# main.net
KiCad netlist of a schematic drawn in EAGLE
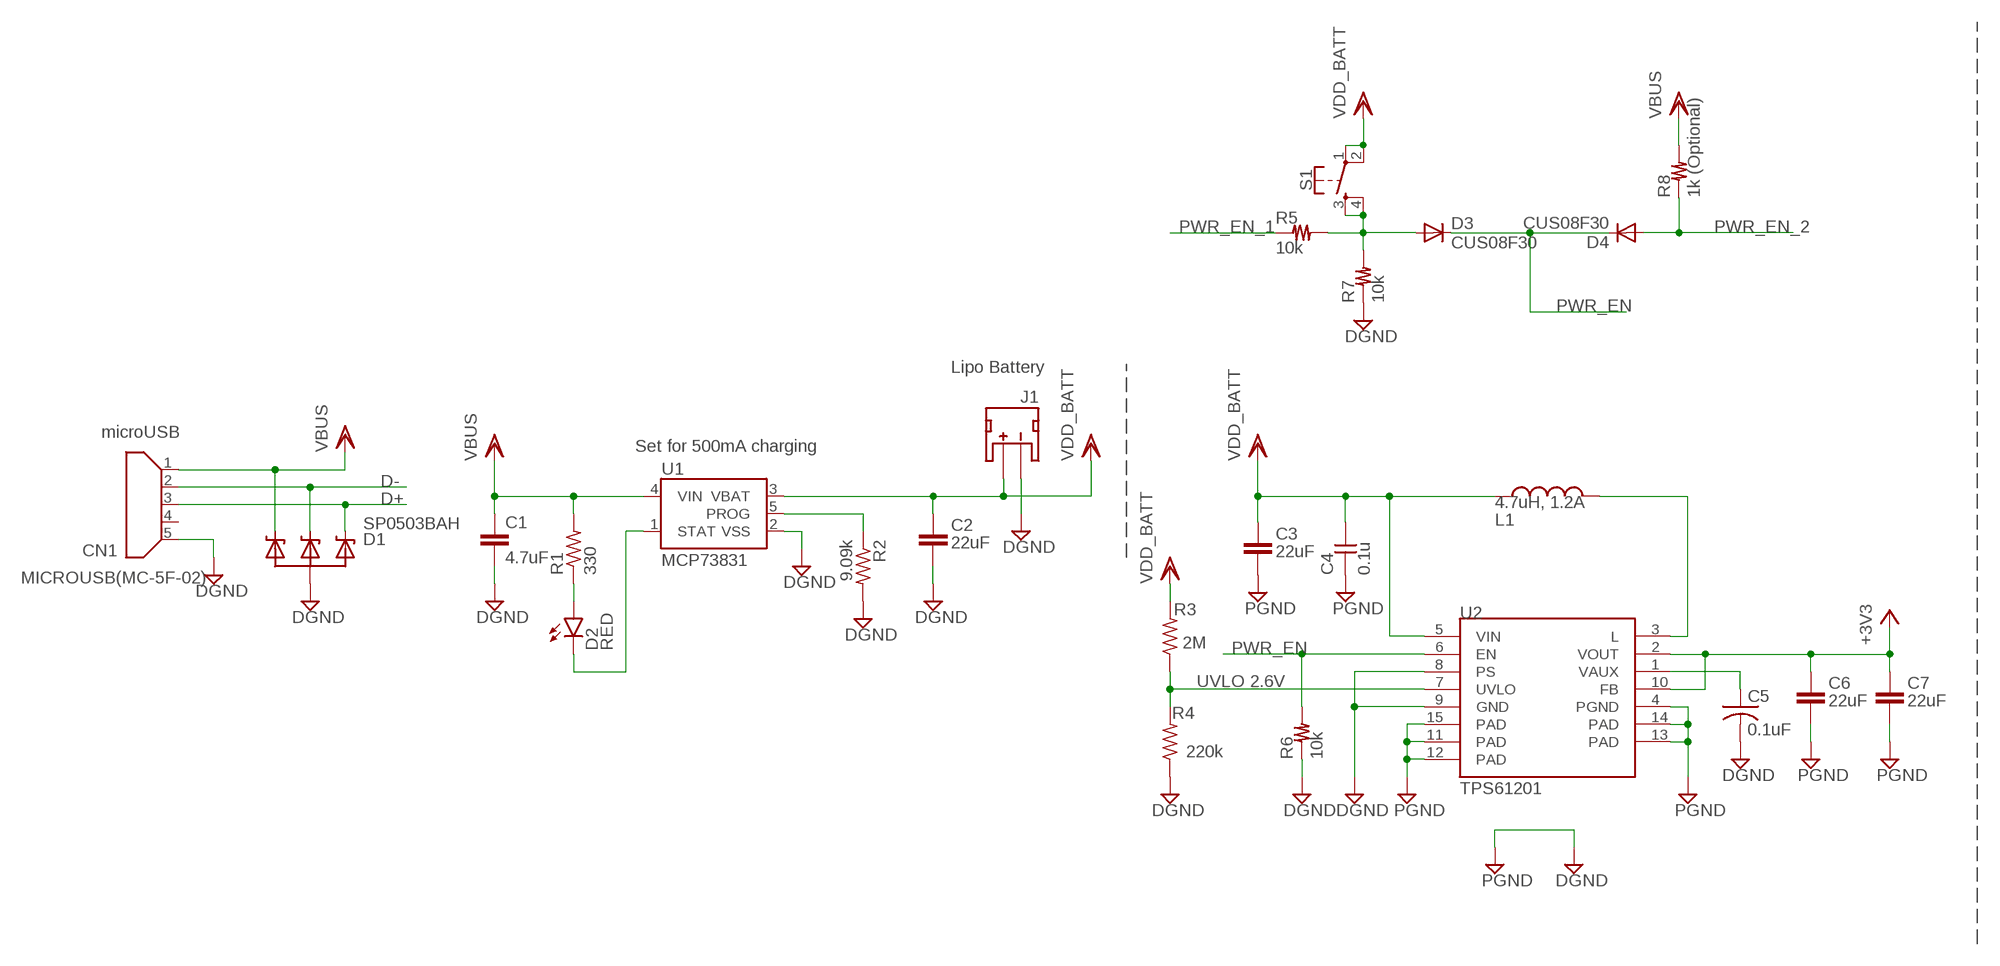
[diagram p0: schematic, sheet 1, part 1 of 2]
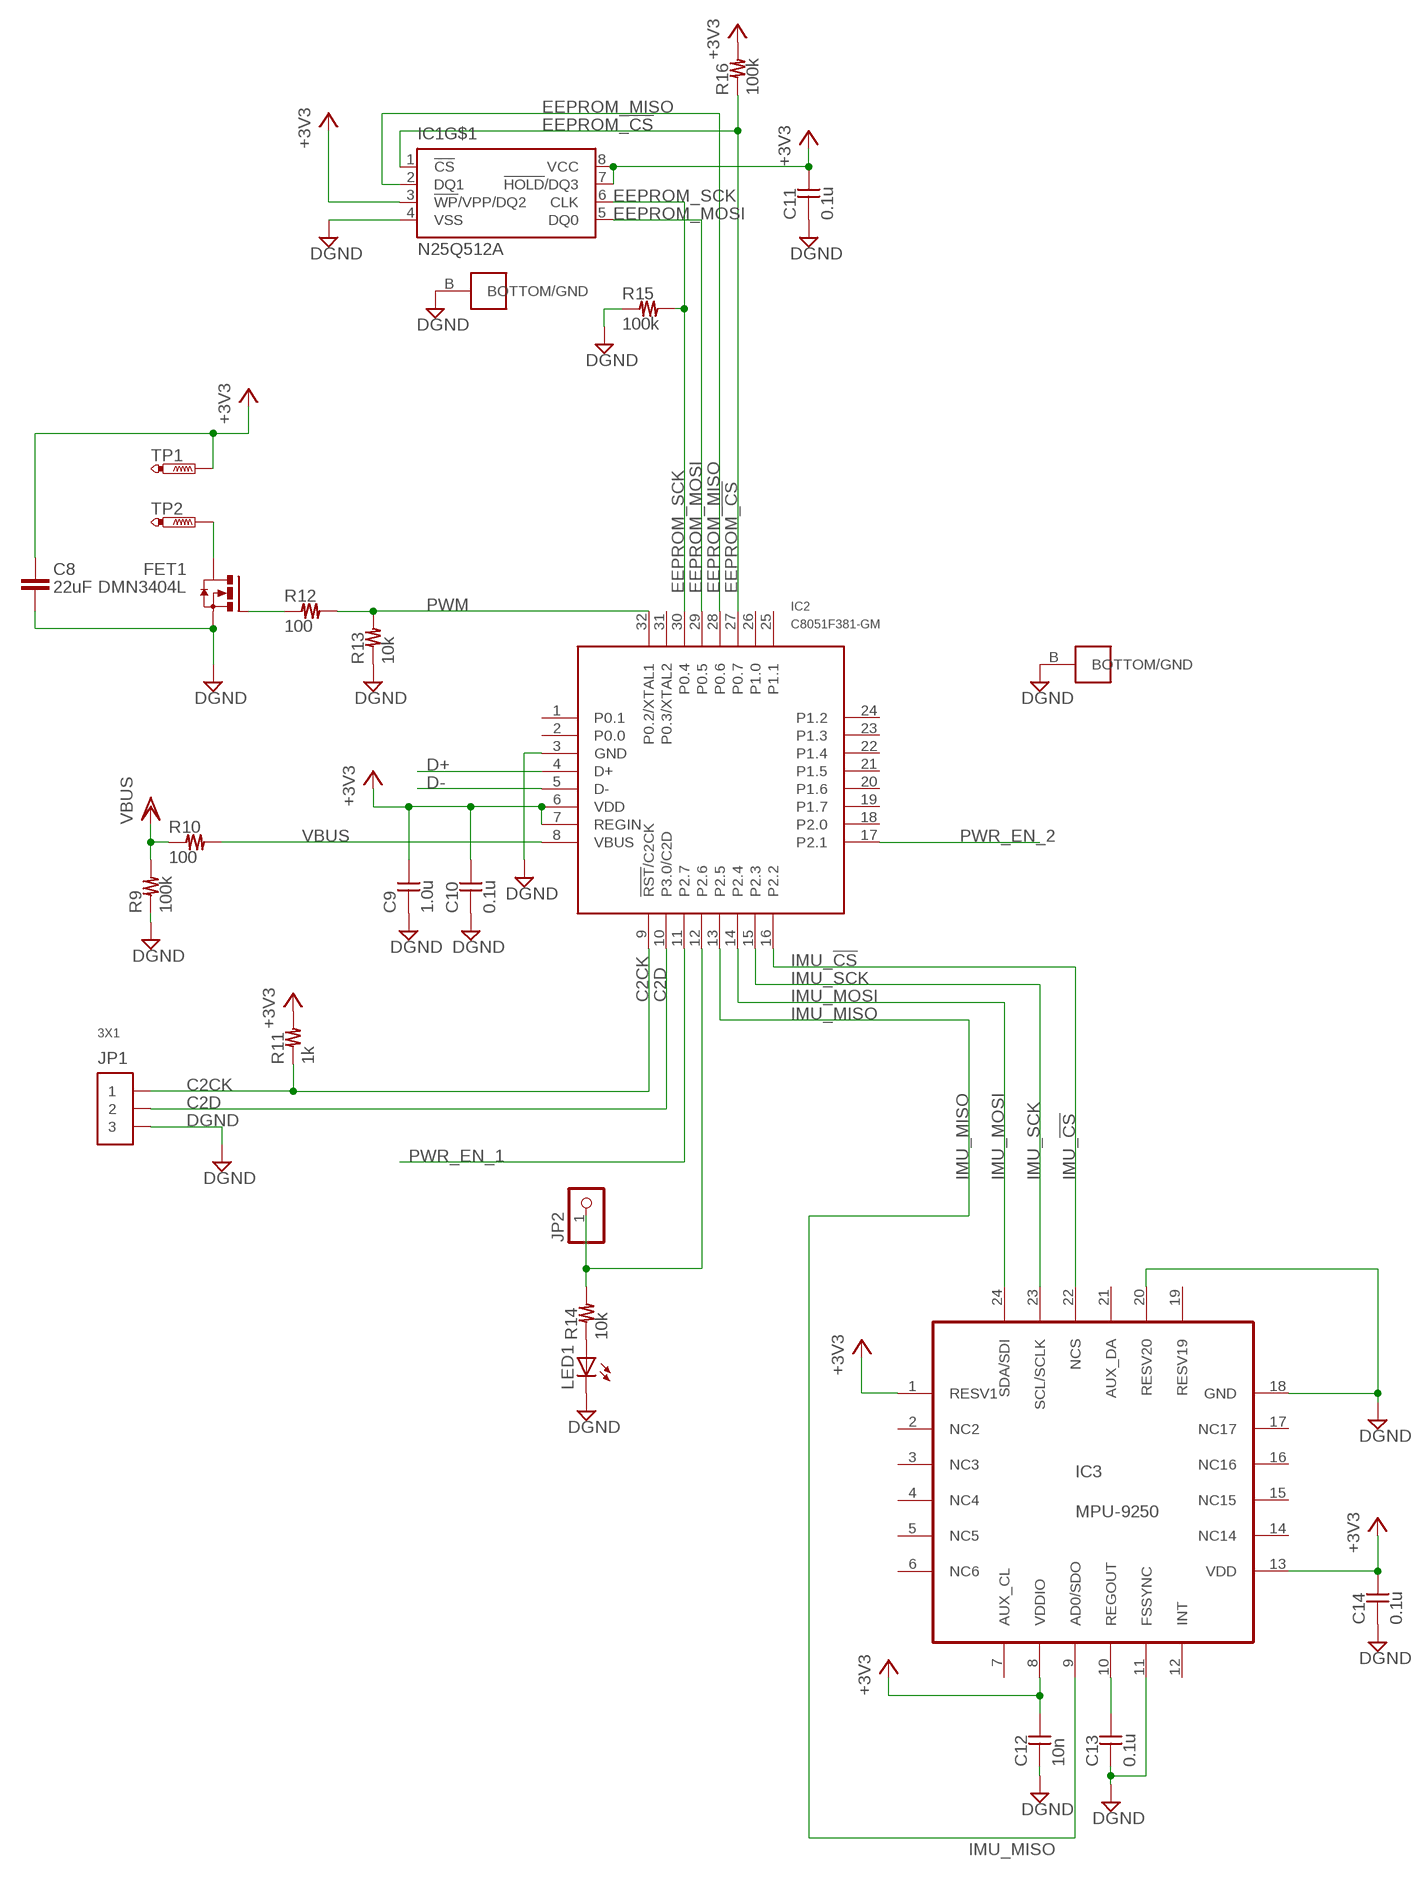
[diagram p1: schematic, sheet 1, part 2 of 2]

(export (version "E")
  (design (tool "Eeschema 10.0.6"))
  (components
    (comp (ref "C1")
      (value "4.7uF")
      (footprint "eagle-import:0603-CAP")
      (libsource (lib "eagle-import") (part "4.7UF-6.3V-10%(0603)0603"))
    )
    (comp (ref "C2")
      (value "22uF")
      (footprint "eagle-import:0805")
      (libsource (lib "eagle-import") (part "CAP0805"))
    )
    (comp (ref "C3")
      (value "22uF")
      (footprint "eagle-import:0805")
      (libsource (lib "eagle-import") (part "CAP0805"))
    )
    (comp (ref "C4")
      (value "0.1u")
      (footprint "eagle-import:1005")
      (libsource (lib "eagle-import") (part "C-1005"))
    )
    (comp (ref "C5")
      (value "0.1uF")
      (footprint "eagle-import:C0402K")
      (libsource (lib "eagle-import") (part "C-USC0402K"))
    )
    (comp (ref "C6")
      (value "22uF")
      (footprint "eagle-import:0805")
      (libsource (lib "eagle-import") (part "CAP0805"))
    )
    (comp (ref "C7")
      (value "22uF")
      (footprint "eagle-import:0805")
      (libsource (lib "eagle-import") (part "CAP0805"))
    )
    (comp (ref "C8")
      (value "22uF")
      (footprint "eagle-import:0805")
      (libsource (lib "eagle-import") (part "CAP0805"))
    )
    (comp (ref "C9")
      (value "1.0u")
      (footprint "eagle-import:1005")
      (libsource (lib "eagle-import") (part "C-1005"))
    )
    (comp (ref "C10")
      (value "0.1u")
      (footprint "eagle-import:1005")
      (libsource (lib "eagle-import") (part "C-1005"))
    )
    (comp (ref "C11")
      (value "0.1u")
      (footprint "eagle-import:1005")
      (libsource (lib "eagle-import") (part "C-1005"))
    )
    (comp (ref "C12")
      (value "10n")
      (footprint "eagle-import:1005")
      (libsource (lib "eagle-import") (part "C-1005"))
    )
    (comp (ref "C13")
      (value "0.1u")
      (footprint "eagle-import:1005")
      (libsource (lib "eagle-import") (part "C-1005"))
    )
    (comp (ref "C14")
      (value "0.1u")
      (footprint "eagle-import:1005")
      (libsource (lib "eagle-import") (part "C-1005"))
    )
    (comp (ref "CN1")
      (value "MICROUSB(MC-5F-02)")
      (footprint "eagle-import:MICROUSB(MC-5F-02)")
      (libsource (lib "eagle-import") (part "MICROUSB(MC-5F-02)"))
    )
    (comp (ref "D1")
      (value "SP0503BAH")
      (footprint "eagle-import:SOT143")
      (libsource (lib "eagle-import") (part "SP0503BAH"))
    )
    (comp (ref "D2")
      (value "RED")
      (footprint "eagle-import:LED-0603")
      (libsource (lib "eagle-import") (part "LED-RED0603"))
    )
    (comp (ref "D3")
      (value "CUS08F30")
      (footprint "eagle-import:SOD323-W")
      (libsource (lib "eagle-import") (part "DIODE-SOD323-W"))
    )
    (comp (ref "D4")
      (value "CUS08F30")
      (footprint "eagle-import:SOD323-W")
      (libsource (lib "eagle-import") (part "DIODE-SOD323-W"))
    )
    (comp (ref "FET1")
      (value "DMN3404L")
      (footprint "eagle-import:SOT23")
      (libsource (lib "eagle-import") (part "DMN3404L"))
    )
    (comp (ref "IC1")
      (value "N25Q512A")
      (footprint "eagle-import:V-PDFN-8")
      (libsource (lib "eagle-import") (part "N25Q512A"))
    )
    (comp (ref "IC2")
      (value "C8051F381-GM")
      (footprint "eagle-import:QFN32")
      (libsource (lib "eagle-import") (part "C8051F381-GM"))
    )
    (comp (ref "IC3")
      (value "MPU-9250")
      (footprint "eagle-import:QFN-24")
      (libsource (lib "eagle-import") (part "MPU-9250"))
    )
    (comp (ref "J1")
      (value "JST")
      (footprint "eagle-import:JST-2-SMD")
      (libsource (lib "eagle-import") (part "JST_2MM_MALE"))
    )
    (comp (ref "JP1")
      (value "3X1")
      (footprint "eagle-import:MA3-1")
      (libsource (lib "eagle-import") (part "3X1"))
    )
    (comp (ref "JP2")
      (value "PINHD-1X1")
      (footprint "eagle-import:1X01")
      (libsource (lib "eagle-import") (part "PINHD-1X1"))
    )
    (comp (ref "L1")
      (value "4.7uH, 1.2A")
      (footprint "eagle-import:CDRH2D09")
      (libsource (lib "eagle-import") (part "INDUCTOR."))
    )
    (comp (ref "LED1")
      (value "LED1608O")
      (footprint "eagle-import:1608-OLI")
      (libsource (lib "eagle-import") (part "LED1608O"))
    )
    (comp (ref "R1")
      (value "330")
      (footprint "eagle-import:R0402")
      (libsource (lib "eagle-import") (part "R-US_R0402"))
    )
    (comp (ref "R2")
      (value "9.09k")
      (footprint "eagle-import:R0402")
      (libsource (lib "eagle-import") (part "R-US_R0402"))
    )
    (comp (ref "R3")
      (value "2M")
      (footprint "eagle-import:R0402")
      (libsource (lib "eagle-import") (part "R-US_R0402"))
    )
    (comp (ref "R4")
      (value "220k")
      (footprint "eagle-import:R0402")
      (libsource (lib "eagle-import") (part "R-US_R0402"))
    )
    (comp (ref "R5")
      (value "10k")
      (footprint "eagle-import:1005")
      (libsource (lib "eagle-import") (part "R-1005"))
    )
    (comp (ref "R6")
      (value "10k")
      (footprint "eagle-import:1005")
      (libsource (lib "eagle-import") (part "R-1005"))
    )
    (comp (ref "R7")
      (value "10k")
      (footprint "eagle-import:1005")
      (libsource (lib "eagle-import") (part "R-1005"))
    )
    (comp (ref "R8")
      (value "1k (Optional)")
      (footprint "eagle-import:1005")
      (libsource (lib "eagle-import") (part "R-1005"))
    )
    (comp (ref "R9")
      (value "100k")
      (footprint "eagle-import:1005")
      (libsource (lib "eagle-import") (part "R-1005"))
    )
    (comp (ref "R10")
      (value "100")
      (footprint "eagle-import:1005")
      (libsource (lib "eagle-import") (part "R-1005"))
    )
    (comp (ref "R11")
      (value "1k")
      (footprint "eagle-import:1005")
      (libsource (lib "eagle-import") (part "R-1005"))
    )
    (comp (ref "R12")
      (value "100")
      (footprint "eagle-import:1005")
      (libsource (lib "eagle-import") (part "R-1005"))
    )
    (comp (ref "R13")
      (value "10k")
      (footprint "eagle-import:1005")
      (libsource (lib "eagle-import") (part "R-1005"))
    )
    (comp (ref "R14")
      (value "10k")
      (footprint "eagle-import:1005")
      (libsource (lib "eagle-import") (part "R-1005"))
    )
    (comp (ref "R15")
      (value "100k")
      (footprint "eagle-import:1005")
      (libsource (lib "eagle-import") (part "R-1005"))
    )
    (comp (ref "R16")
      (value "100k")
      (footprint "eagle-import:1005")
      (libsource (lib "eagle-import") (part "R-1005"))
    )
    (comp (ref "S1")
      (value "MOMENTARY-SWITCH-SPST-2-SMD-4.6X2.8MM")
      (footprint "eagle-import:TACTILE_SWITCH_SMD_4.6X2.8MM")
      (libsource (lib "eagle-import") (part "MOMENTARY-SWITCH-SPST-2-SMD-4.6X2.8MM"))
    )
    (comp (ref "TP1")
      (value "PTR1TP10R")
      (footprint "eagle-import:TP10R")
      (libsource (lib "eagle-import") (part "PTR1TP10R"))
    )
    (comp (ref "TP2")
      (value "PTR1TP10R")
      (footprint "eagle-import:TP10R")
      (libsource (lib "eagle-import") (part "PTR1TP10R"))
    )
    (comp (ref "U1")
      (value "MCP73831")
      (footprint "eagle-import:SOT23-5")
      (libsource (lib "eagle-import") (part "MCP73831"))
    )
    (comp (ref "U2")
      (value "TPS61201")
      (footprint "eagle-import:QFN-10_PAD")
      (libsource (lib "eagle-import") (part "TPS61200"))
    )
  )
  (nets
    (net (code "1") (name "+3V3") (class "Default")
      (node (ref "C10") (pin "P$2") (pinfunction "P$2_P$2") (pintype "passive"))
      (node (ref "C11") (pin "P$2") (pinfunction "P$2_P$2") (pintype "passive"))
      (node (ref "C12") (pin "P$2") (pinfunction "P$2_P$2") (pintype "passive"))
      (node (ref "C14") (pin "P$2") (pinfunction "P$2_P$2") (pintype "passive"))
      (node (ref "C6") (pin "1") (pinfunction "1_1") (pintype "passive"))
      (node (ref "C7") (pin "1") (pinfunction "1_1") (pintype "passive"))
      (node (ref "C8") (pin "1") (pinfunction "1_1") (pintype "passive"))
      (node (ref "C9") (pin "P$2") (pinfunction "P$2_P$2") (pintype "passive"))
      (node (ref "IC1") (pin "3") (pinfunction "~{WP}/VPP/DQ2_3") (pintype "bidirectional"))
      (node (ref "IC1") (pin "7") (pinfunction "~{HOLD}/DQ3_7") (pintype "bidirectional"))
      (node (ref "IC1") (pin "8") (pinfunction "VCC_8") (pintype "power_in"))
      (node (ref "IC2") (pin "6") (pinfunction "VDD_6") (pintype "bidirectional"))
      (node (ref "IC2") (pin "7") (pinfunction "REGIN_7") (pintype "bidirectional"))
      (node (ref "IC3") (pin "1") (pinfunction "RESV1_1") (pintype "input"))
      (node (ref "IC3") (pin "13") (pinfunction "VDD_13") (pintype "power_in"))
      (node (ref "IC3") (pin "8") (pinfunction "VDDIO_8") (pintype "power_in"))
      (node (ref "R11") (pin "P$2") (pinfunction "P$2_P$2") (pintype "passive"))
      (node (ref "R16") (pin "P$2") (pinfunction "P$2_P$2") (pintype "passive"))
      (node (ref "TP1") (pin "TP") (pinfunction "TP_TP") (pintype "input"))
      (node (ref "U2") (pin "10") (pinfunction "FB_10") (pintype "passive"))
      (node (ref "U2") (pin "2") (pinfunction "VOUT_2") (pintype "passive"))
    )
    (net (code "2") (name "/C2CK") (class "Default")
      (node (ref "IC2") (pin "9") (pinfunction "~{RST}/C2CK_9") (pintype "bidirectional"))
      (node (ref "JP1") (pin "1") (pinfunction "1_1") (pintype "passive"))
      (node (ref "R11") (pin "P$1") (pinfunction "P$1_P$1") (pintype "passive"))
    )
    (net (code "3") (name "/C2D") (class "Default")
      (node (ref "IC2") (pin "10") (pinfunction "P3.0/C2D_10") (pintype "bidirectional"))
      (node (ref "JP1") (pin "2") (pinfunction "2_2") (pintype "passive"))
    )
    (net (code "4") (name "/D+") (class "Default")
      (node (ref "CN1") (pin "3") (pinfunction "P$3_3") (pintype "passive"))
      (node (ref "D1") (pin "2") (pinfunction "2_2") (pintype "passive"))
      (node (ref "IC2") (pin "4") (pinfunction "D+_4") (pintype "bidirectional"))
    )
    (net (code "5") (name "/D-") (class "Default")
      (node (ref "CN1") (pin "2") (pinfunction "P$2_2") (pintype "passive"))
      (node (ref "D1") (pin "3") (pinfunction "3_3") (pintype "passive"))
      (node (ref "IC2") (pin "5") (pinfunction "D-_5") (pintype "bidirectional"))
    )
    (net (code "6") (name "/EEPROM_MISO") (class "Default")
      (node (ref "IC1") (pin "2") (pinfunction "DQ1_2") (pintype "bidirectional"))
      (node (ref "IC2") (pin "28") (pinfunction "P0.6_28") (pintype "bidirectional"))
    )
    (net (code "7") (name "/EEPROM_MOSI") (class "Default")
      (node (ref "IC1") (pin "5") (pinfunction "DQ0_5") (pintype "bidirectional"))
      (node (ref "IC2") (pin "29") (pinfunction "P0.5_29") (pintype "bidirectional"))
    )
    (net (code "8") (name "/EEPROM_SCK") (class "Default")
      (node (ref "IC1") (pin "6") (pinfunction "CLK_6") (pintype "input"))
      (node (ref "IC2") (pin "30") (pinfunction "P0.4_30") (pintype "bidirectional"))
      (node (ref "R15") (pin "P$2") (pinfunction "P$2_P$2") (pintype "passive"))
    )
    (net (code "9") (name "/EEPROM_~{CS}") (class "Default")
      (node (ref "IC1") (pin "1") (pinfunction "~{CS}_1") (pintype "input"))
      (node (ref "IC2") (pin "27") (pinfunction "P0.7_27") (pintype "bidirectional"))
      (node (ref "R16") (pin "P$1") (pinfunction "P$1_P$1") (pintype "passive"))
    )
    (net (code "10") (name "/IMU_MISO") (class "Default")
      (node (ref "IC2") (pin "13") (pinfunction "P2.5_13") (pintype "bidirectional"))
      (node (ref "IC3") (pin "9") (pinfunction "AD0/SDO_9") (pintype "bidirectional"))
    )
    (net (code "11") (name "/IMU_MOSI") (class "Default")
      (node (ref "IC2") (pin "14") (pinfunction "P2.4_14") (pintype "bidirectional"))
      (node (ref "IC3") (pin "24") (pinfunction "SDA/SDI_24") (pintype "input"))
    )
    (net (code "12") (name "/IMU_SCK") (class "Default")
      (node (ref "IC2") (pin "15") (pinfunction "P2.3_15") (pintype "bidirectional"))
      (node (ref "IC3") (pin "23") (pinfunction "SCL/SCLK_23") (pintype "input"))
    )
    (net (code "13") (name "/IMU_~{CS}") (class "Default")
      (node (ref "IC2") (pin "16") (pinfunction "P2.2_16") (pintype "bidirectional"))
      (node (ref "IC3") (pin "22") (pinfunction "NCS_22") (pintype "input"))
    )
    (net (code "14") (name "/PWM") (class "Default")
      (node (ref "IC2") (pin "32") (pinfunction "P0.2/XTAL1_32") (pintype "bidirectional"))
      (node (ref "R12") (pin "P$2") (pinfunction "P$2_P$2") (pintype "passive"))
      (node (ref "R13") (pin "P$2") (pinfunction "P$2_P$2") (pintype "passive"))
    )
    (net (code "15") (name "/PWR_EN") (class "Default")
      (node (ref "D3") (pin "C") (pinfunction "C_C") (pintype "passive"))
      (node (ref "D4") (pin "C") (pinfunction "C_C") (pintype "passive"))
      (node (ref "R6") (pin "P$2") (pinfunction "P$2_P$2") (pintype "passive"))
      (node (ref "U2") (pin "6") (pinfunction "EN_6") (pintype "input"))
    )
    (net (code "16") (name "/PWR_EN_1") (class "Default")
      (node (ref "IC2") (pin "11") (pinfunction "P2.7_11") (pintype "bidirectional"))
      (node (ref "R5") (pin "P$1") (pinfunction "P$1_P$1") (pintype "passive"))
    )
    (net (code "17") (name "/PWR_EN_2") (class "Default")
      (node (ref "D4") (pin "A") (pinfunction "A_A") (pintype "passive"))
      (node (ref "IC2") (pin "17") (pinfunction "P2.1_17") (pintype "bidirectional"))
      (node (ref "R8") (pin "P$1") (pinfunction "P$1_P$1") (pintype "passive"))
    )
    (net (code "18") (name "DGND") (class "Default")
      (node (ref "C1") (pin "2") (pinfunction "2_2") (pintype "passive"))
      (node (ref "C10") (pin "P$1") (pinfunction "P$1_P$1") (pintype "passive"))
      (node (ref "C11") (pin "P$1") (pinfunction "P$1_P$1") (pintype "passive"))
      (node (ref "C12") (pin "P$1") (pinfunction "P$1_P$1") (pintype "passive"))
      (node (ref "C13") (pin "P$1") (pinfunction "P$1_P$1") (pintype "passive"))
      (node (ref "C14") (pin "P$1") (pinfunction "P$1_P$1") (pintype "passive"))
      (node (ref "C2") (pin "2") (pinfunction "2_2") (pintype "passive"))
      (node (ref "C3") (pin "2") (pinfunction "2_2") (pintype "passive"))
      (node (ref "C4") (pin "P$1") (pinfunction "P$1_P$1") (pintype "passive"))
      (node (ref "C5") (pin "2") (pinfunction "2_2") (pintype "passive"))
      (node (ref "C6") (pin "2") (pinfunction "2_2") (pintype "passive"))
      (node (ref "C7") (pin "2") (pinfunction "2_2") (pintype "passive"))
      (node (ref "C8") (pin "2") (pinfunction "2_2") (pintype "passive"))
      (node (ref "C9") (pin "P$1") (pinfunction "P$1_P$1") (pintype "passive"))
      (node (ref "CN1") (pin "5") (pinfunction "P$5_5") (pintype "passive"))
      (node (ref "D1") (pin "1") (pinfunction "1_1") (pintype "passive"))
      (node (ref "FET1") (pin "S") (pinfunction "S_S") (pintype "passive"))
      (node (ref "IC1") (pin "4") (pinfunction "VSS_4") (pintype "power_in"))
      (node (ref "IC1") (pin "B") (pinfunction "BOTTOM/GND_B") (pintype "power_in"))
      (node (ref "IC2") (pin "3") (pinfunction "GND_3") (pintype "bidirectional"))
      (node (ref "IC2") (pin "B") (pinfunction "BOTTOM/GND_B") (pintype "power_in"))
      (node (ref "IC3") (pin "11") (pinfunction "FSSYNC_11") (pintype "input"))
      (node (ref "IC3") (pin "18") (pinfunction "GND_18") (pintype "power_in"))
      (node (ref "IC3") (pin "20") (pinfunction "RESV20_20") (pintype "input"))
      (node (ref "J1") (pin "1") (pinfunction "-_1") (pintype "bidirectional"))
      (node (ref "JP1") (pin "3") (pinfunction "3_3") (pintype "passive"))
      (node (ref "LED1") (pin "K") (pinfunction "K_K") (pintype "passive"))
      (node (ref "R13") (pin "P$1") (pinfunction "P$1_P$1") (pintype "passive"))
      (node (ref "R15") (pin "P$1") (pinfunction "P$1_P$1") (pintype "passive"))
      (node (ref "R2") (pin "2") (pinfunction "2_2") (pintype "passive"))
      (node (ref "R4") (pin "1") (pinfunction "1_1") (pintype "passive"))
      (node (ref "R6") (pin "P$1") (pinfunction "P$1_P$1") (pintype "passive"))
      (node (ref "R7") (pin "P$1") (pinfunction "P$1_P$1") (pintype "passive"))
      (node (ref "R9") (pin "P$1") (pinfunction "P$1_P$1") (pintype "passive"))
      (node (ref "U1") (pin "2") (pinfunction "VSS_2") (pintype "power_in"))
      (node (ref "U2") (pin "11") (pinfunction "PAD_11") (pintype "power_in"))
      (node (ref "U2") (pin "12") (pinfunction "PAD_12") (pintype "power_in"))
      (node (ref "U2") (pin "13") (pinfunction "PAD_13") (pintype "power_in"))
      (node (ref "U2") (pin "14") (pinfunction "PAD_14") (pintype "power_in"))
      (node (ref "U2") (pin "15") (pinfunction "PAD_15") (pintype "power_in"))
      (node (ref "U2") (pin "4") (pinfunction "PGND_4") (pintype "power_in"))
      (node (ref "U2") (pin "8") (pinfunction "PS_8") (pintype "input"))
      (node (ref "U2") (pin "9") (pinfunction "GND_9") (pintype "power_in"))
    )
    (net (code "19") (name "Net-(D2-PadA)") (class "Default")
      (node (ref "D2") (pin "A") (pinfunction "A_A") (pintype "passive"))
      (node (ref "R1") (pin "1") (pinfunction "1_1") (pintype "passive"))
    )
    (net (code "20") (name "Net-(D3-PadA)") (class "Default")
      (node (ref "D3") (pin "A") (pinfunction "A_A") (pintype "passive"))
      (node (ref "R5") (pin "P$2") (pinfunction "P$2_P$2") (pintype "passive"))
      (node (ref "R7") (pin "P$2") (pinfunction "P$2_P$2") (pintype "passive"))
      (node (ref "S1") (pin "3") (pinfunction "3_3") (pintype "passive"))
      (node (ref "S1") (pin "4") (pinfunction "4_4") (pintype "passive"))
    )
    (net (code "21") (name "Net-(FET1-PadD)") (class "Default")
      (node (ref "FET1") (pin "D") (pinfunction "D_D") (pintype "passive"))
      (node (ref "TP2") (pin "TP") (pinfunction "TP_TP") (pintype "input"))
    )
    (net (code "22") (name "Net-(FET1-PadG)") (class "Default")
      (node (ref "FET1") (pin "G") (pinfunction "G_G") (pintype "passive"))
      (node (ref "R12") (pin "P$1") (pinfunction "P$1_P$1") (pintype "passive"))
    )
    (net (code "23") (name "Net-(IC2A-P2.6)") (class "Default")
      (node (ref "IC2") (pin "12") (pinfunction "P2.6_12") (pintype "bidirectional"))
      (node (ref "JP2") (pin "1") (pinfunction "1_1") (pintype "passive"))
      (node (ref "R14") (pin "P$2") (pinfunction "P$2_P$2") (pintype "passive"))
    )
    (net (code "24") (name "Net-(IC2A-VBUS)") (class "Default")
      (node (ref "IC2") (pin "8") (pinfunction "VBUS_8") (pintype "bidirectional"))
      (node (ref "R10") (pin "P$2") (pinfunction "P$2_P$2") (pintype "passive"))
    )
    (net (code "25") (name "Net-(IC3-REGOUT)") (class "Default")
      (node (ref "C13") (pin "P$2") (pinfunction "P$2_P$2") (pintype "passive"))
      (node (ref "IC3") (pin "10") (pinfunction "REGOUT_10") (pintype "bidirectional"))
    )
    (net (code "26") (name "Net-(L1-1)") (class "Default")
      (node (ref "L1") (pin "P$1") (pinfunction "1_P$1") (pintype "passive"))
      (node (ref "U2") (pin "3") (pinfunction "L_3") (pintype "passive"))
    )
    (net (code "27") (name "Net-(LED1-PadA)") (class "Default")
      (node (ref "LED1") (pin "A") (pinfunction "A_A") (pintype "passive"))
      (node (ref "R14") (pin "P$1") (pinfunction "P$1_P$1") (pintype "passive"))
    )
    (net (code "28") (name "Net-(U1-PROG)") (class "Default")
      (node (ref "R2") (pin "1") (pinfunction "1_1") (pintype "passive"))
      (node (ref "U1") (pin "5") (pinfunction "PROG_5") (pintype "input"))
    )
    (net (code "29") (name "Net-(U1-STAT)") (class "Default")
      (node (ref "D2") (pin "C") (pinfunction "C_C") (pintype "passive"))
      (node (ref "U1") (pin "1") (pinfunction "STAT_1") (pintype "output"))
    )
    (net (code "30") (name "Net-(U2-UVLO)") (class "Default")
      (node (ref "R3") (pin "1") (pinfunction "1_1") (pintype "passive"))
      (node (ref "R4") (pin "2") (pinfunction "2_2") (pintype "passive"))
      (node (ref "U2") (pin "7") (pinfunction "UVLO_7") (pintype "passive"))
    )
    (net (code "31") (name "Net-(U2-VAUX)") (class "Default")
      (node (ref "C5") (pin "1") (pinfunction "1_1") (pintype "passive"))
      (node (ref "U2") (pin "1") (pinfunction "VAUX_1") (pintype "passive"))
    )
    (net (code "32") (name "VBUS") (class "Default")
      (node (ref "C1") (pin "1") (pinfunction "1_1") (pintype "passive"))
      (node (ref "CN1") (pin "1") (pinfunction "P$1_1") (pintype "passive"))
      (node (ref "D1") (pin "4") (pinfunction "4_4") (pintype "passive"))
      (node (ref "R1") (pin "2") (pinfunction "2_2") (pintype "passive"))
      (node (ref "R10") (pin "P$1") (pinfunction "P$1_P$1") (pintype "passive"))
      (node (ref "R8") (pin "P$2") (pinfunction "P$2_P$2") (pintype "passive"))
      (node (ref "R9") (pin "P$2") (pinfunction "P$2_P$2") (pintype "passive"))
      (node (ref "U1") (pin "4") (pinfunction "VIN_4") (pintype "power_in"))
    )
    (net (code "33") (name "VDD_BATT") (class "Default")
      (node (ref "C2") (pin "1") (pinfunction "1_1") (pintype "passive"))
      (node (ref "C3") (pin "1") (pinfunction "1_1") (pintype "passive"))
      (node (ref "C4") (pin "P$2") (pinfunction "P$2_P$2") (pintype "passive"))
      (node (ref "J1") (pin "2") (pinfunction "+_2") (pintype "bidirectional"))
      (node (ref "L1") (pin "P$2") (pinfunction "2_P$2") (pintype "passive"))
      (node (ref "R3") (pin "2") (pinfunction "2_2") (pintype "passive"))
      (node (ref "S1") (pin "1") (pinfunction "1_1") (pintype "passive"))
      (node (ref "S1") (pin "2") (pinfunction "2_2") (pintype "passive"))
      (node (ref "U1") (pin "3") (pinfunction "VBAT_3") (pintype "power_in"))
      (node (ref "U2") (pin "5") (pinfunction "VIN_5") (pintype "power_in"))
    )
    (net (code "34") (name "unconnected-(CN1-P$4-Pad4)") (class "Default")
      (node (ref "CN1") (pin "4") (pinfunction "P$4_4") (pintype "passive"))
    )
    (net (code "35") (name "unconnected-(IC2A-P0.0-Pad2)") (class "Default")
      (node (ref "IC2") (pin "2") (pinfunction "P0.0_2") (pintype "bidirectional"))
    )
    (net (code "36") (name "unconnected-(IC2A-P0.1-Pad1)") (class "Default")
      (node (ref "IC2") (pin "1") (pinfunction "P0.1_1") (pintype "bidirectional"))
    )
    (net (code "37") (name "unconnected-(IC2A-P0.3{slash}XTAL2-Pad31)") (class "Default")
      (node (ref "IC2") (pin "31") (pinfunction "P0.3/XTAL2_31") (pintype "bidirectional"))
    )
    (net (code "38") (name "unconnected-(IC2A-P1.0-Pad26)") (class "Default")
      (node (ref "IC2") (pin "26") (pinfunction "P1.0_26") (pintype "bidirectional"))
    )
    (net (code "39") (name "unconnected-(IC2A-P1.1-Pad25)") (class "Default")
      (node (ref "IC2") (pin "25") (pinfunction "P1.1_25") (pintype "bidirectional"))
    )
    (net (code "40") (name "unconnected-(IC2A-P1.2-Pad24)") (class "Default")
      (node (ref "IC2") (pin "24") (pinfunction "P1.2_24") (pintype "bidirectional"))
    )
    (net (code "41") (name "unconnected-(IC2A-P1.3-Pad23)") (class "Default")
      (node (ref "IC2") (pin "23") (pinfunction "P1.3_23") (pintype "bidirectional"))
    )
    (net (code "42") (name "unconnected-(IC2A-P1.4-Pad22)") (class "Default")
      (node (ref "IC2") (pin "22") (pinfunction "P1.4_22") (pintype "bidirectional"))
    )
    (net (code "43") (name "unconnected-(IC2A-P1.5-Pad21)") (class "Default")
      (node (ref "IC2") (pin "21") (pinfunction "P1.5_21") (pintype "bidirectional"))
    )
    (net (code "44") (name "unconnected-(IC2A-P1.6-Pad20)") (class "Default")
      (node (ref "IC2") (pin "20") (pinfunction "P1.6_20") (pintype "bidirectional"))
    )
    (net (code "45") (name "unconnected-(IC2A-P1.7-Pad19)") (class "Default")
      (node (ref "IC2") (pin "19") (pinfunction "P1.7_19") (pintype "bidirectional"))
    )
    (net (code "46") (name "unconnected-(IC2A-P2.0-Pad18)") (class "Default")
      (node (ref "IC2") (pin "18") (pinfunction "P2.0_18") (pintype "bidirectional"))
    )
    (net (code "47") (name "unconnected-(IC3-AUX_CL-Pad7)") (class "Default")
      (node (ref "IC3") (pin "7") (pinfunction "AUX_CL_7") (pintype "output"))
    )
    (net (code "48") (name "unconnected-(IC3-AUX_DA-Pad21)") (class "Default")
      (node (ref "IC3") (pin "21") (pinfunction "AUX_DA_21") (pintype "bidirectional"))
    )
    (net (code "49") (name "unconnected-(IC3-INT-Pad12)") (class "Default")
      (node (ref "IC3") (pin "12") (pinfunction "INT_12") (pintype "output"))
    )
    (net (code "50") (name "unconnected-(IC3-NC2-Pad2)") (class "Default")
      (node (ref "IC3") (pin "2") (pinfunction "NC2_2") (pintype "no_connect"))
    )
    (net (code "51") (name "unconnected-(IC3-NC3-Pad3)") (class "Default")
      (node (ref "IC3") (pin "3") (pinfunction "NC3_3") (pintype "no_connect"))
    )
    (net (code "52") (name "unconnected-(IC3-NC4-Pad4)") (class "Default")
      (node (ref "IC3") (pin "4") (pinfunction "NC4_4") (pintype "no_connect"))
    )
    (net (code "53") (name "unconnected-(IC3-NC5-Pad5)") (class "Default")
      (node (ref "IC3") (pin "5") (pinfunction "NC5_5") (pintype "no_connect"))
    )
    (net (code "54") (name "unconnected-(IC3-NC6-Pad6)") (class "Default")
      (node (ref "IC3") (pin "6") (pinfunction "NC6_6") (pintype "no_connect"))
    )
    (net (code "55") (name "unconnected-(IC3-NC14-Pad14)") (class "Default")
      (node (ref "IC3") (pin "14") (pinfunction "NC14_14") (pintype "no_connect"))
    )
    (net (code "56") (name "unconnected-(IC3-NC15-Pad15)") (class "Default")
      (node (ref "IC3") (pin "15") (pinfunction "NC15_15") (pintype "no_connect"))
    )
    (net (code "57") (name "unconnected-(IC3-NC16-Pad16)") (class "Default")
      (node (ref "IC3") (pin "16") (pinfunction "NC16_16") (pintype "no_connect"))
    )
    (net (code "58") (name "unconnected-(IC3-NC17-Pad17)") (class "Default")
      (node (ref "IC3") (pin "17") (pinfunction "NC17_17") (pintype "no_connect"))
    )
    (net (code "59") (name "unconnected-(IC3-RESV19-Pad19)") (class "Default")
      (node (ref "IC3") (pin "19") (pinfunction "RESV19_19") (pintype "no_connect"))
    )
    (net (code "60") (name "unconnected-(J1-PAD1-PadNC1)") (class "Default")
      (node (ref "J1") (pin "NC1") (pinfunction "PAD1_NC1") (pintype "bidirectional"))
    )
    (net (code "61") (name "unconnected-(J1-PAD2-PadNC2)") (class "Default")
      (node (ref "J1") (pin "NC2") (pinfunction "PAD2_NC2") (pintype "bidirectional"))
    )
  )
)
